# P-MT3620RDB-1-6_PMU.net
KiCad netlist of a schematic drawn in Altium Designer
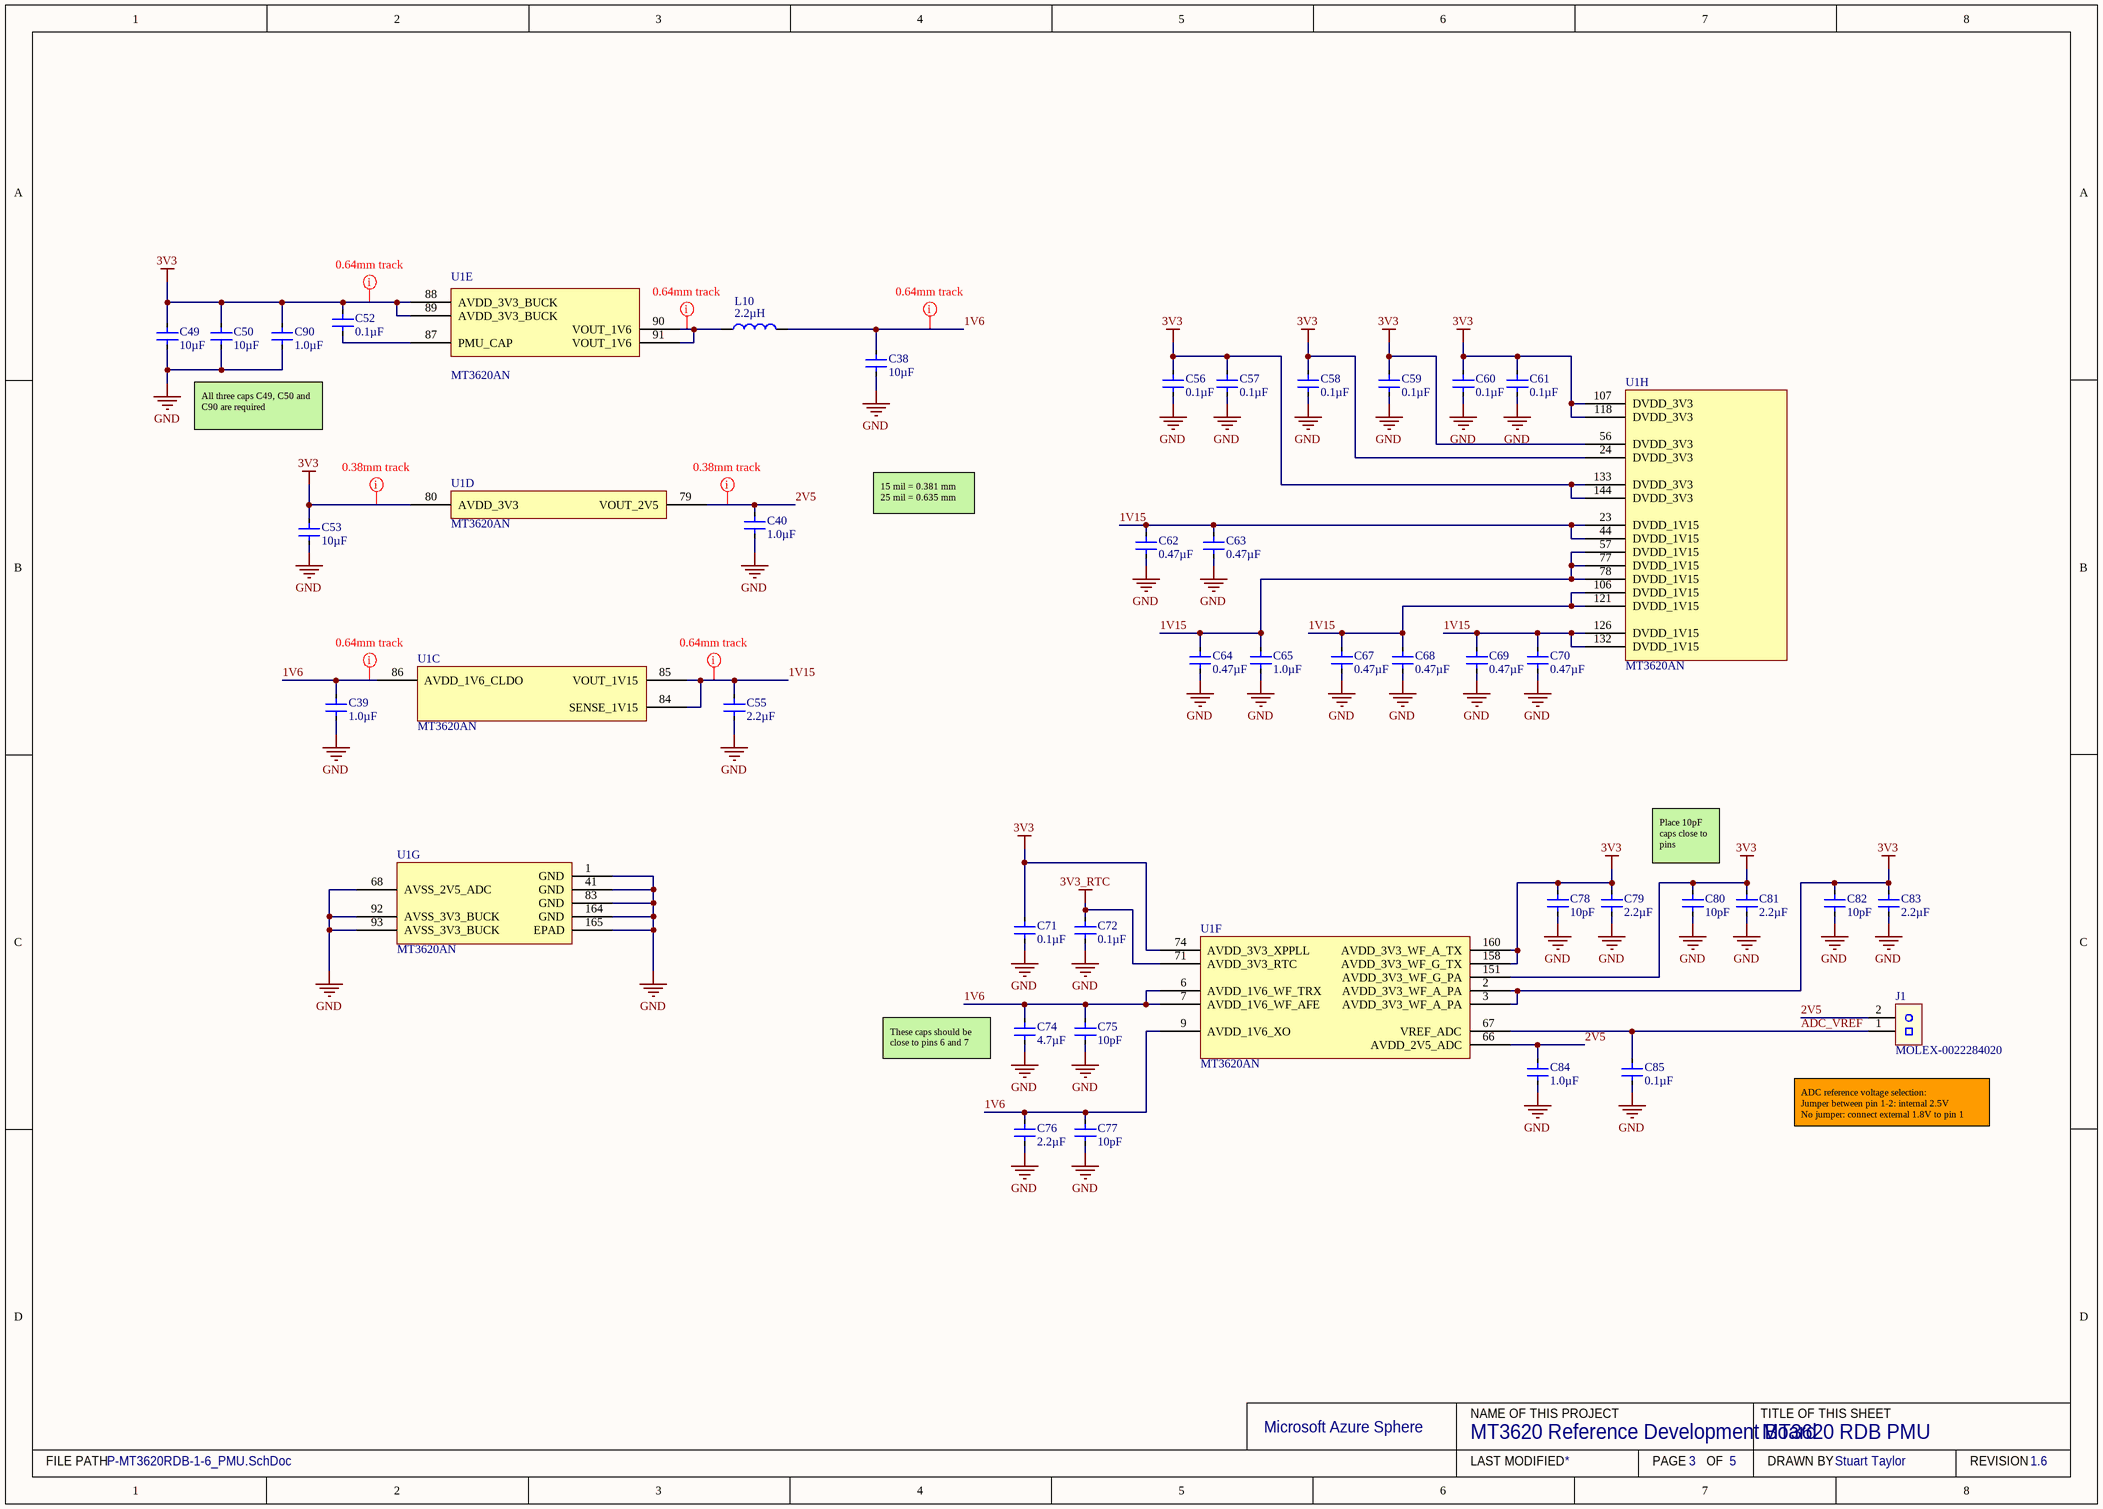
[diagram p0: P-MT3620RDB-1-6_PMU.SchDoc]

(export (version "E")
  (design (tool "Eeschema 10.0.6"))
  (components
    (comp (ref "C38")
      (value "10µF")
      (footprint "CAPC1608-EIA0603-1MM-MED")
      (description "CAP CER 10UF 25V 20% X5R 0603")
      (fields
        (field (name "MANUFACTURER") "TDK Corporation")
        (field (name "MANUFACTURER PART NUMBER") "C1608X5R1E106M080AC")
        (field (name "CAPACITANCE") "10µF")
      )
      (libsource (lib "TDK-Capacitor_C_0603") (part "10µF 0603 X5R 25V"))
    )
    (comp (ref "C39")
      (value "1.0µF")
      (footprint "CAPC1005-EIA0402 0.55MM MED")
      (description "CAP CER 1UF 35V 10% X5R 0402")
      (fields
        (field (name "MANUFACTURER") "TDK Corporation")
        (field (name "MANUFACTURER PART NUMBER") "C1005X5R1V105K050BC")
        (field (name "CAPACITANCE") "1.0µF")
      )
      (libsource (lib "TDK_Capacitor_C_0402") (part "1.0µF 0402 X5R 35V"))
    )
    (comp (ref "C40")
      (value "1.0µF")
      (footprint "CAPC1005-EIA0402 0.55MM MED")
      (description "CAP CER 1UF 35V 10% X5R 0402")
      (fields
        (field (name "MANUFACTURER") "TDK Corporation")
        (field (name "MANUFACTURER PART NUMBER") "C1005X5R1V105K050BC")
        (field (name "CAPACITANCE") "1.0µF")
      )
      (libsource (lib "TDK_Capacitor_C_0402") (part "1.0µF 0402 X5R 35V"))
    )
    (comp (ref "C49")
      (value "10µF")
      (footprint "CAPC1005-EIA0402 0.55MM MED")
      (description "CAP CER 10UF 6.3V 20% X5R 0402")
      (fields
        (field (name "MANUFACTURER") "TDK Corporation")
        (field (name "MANUFACTURER PART NUMBER") "C1005X5R0J106M050BC")
        (field (name "CAPACITANCE") "10µF")
      )
      (libsource (lib "TDK_Capacitor_C_0402") (part "10µF 0402 X5R 6.3V"))
    )
    (comp (ref "C50")
      (value "10µF")
      (footprint "CAPC1005-EIA0402 0.55MM MED")
      (description "CAP CER 10UF 6.3V 20% X5R 0402")
      (fields
        (field (name "MANUFACTURER") "TDK Corporation")
        (field (name "MANUFACTURER PART NUMBER") "C1005X5R0J106M050BC")
        (field (name "CAPACITANCE") "10µF")
      )
      (libsource (lib "TDK_Capacitor_C_0402") (part "10µF 0402 X5R 6.3V"))
    )
    (comp (ref "C52")
      (value "0.1µF")
      (footprint "CAPC1005-EIA0402 0.55MM MED")
      (description "CAP CER 0.1UF 50V 10% X7R 0402")
      (fields
        (field (name "MANUFACTURER") "TDK Corporation")
        (field (name "MANUFACTURER PART NUMBER") "C1005X7R1H104K050BB")
        (field (name "CAPACITANCE") "0.1µF")
      )
      (libsource (lib "TDK_Capacitor_C_0402") (part "0.1µF 0402 X7R 50V"))
    )
    (comp (ref "C53")
      (value "10µF")
      (footprint "CAPC1005-EIA0402 0.55MM MED")
      (description "CAP CER 10UF 6.3V 20% X5R 0402")
      (fields
        (field (name "MANUFACTURER") "TDK Corporation")
        (field (name "MANUFACTURER PART NUMBER") "C1005X5R0J106M050BC")
        (field (name "CAPACITANCE") "10µF")
      )
      (libsource (lib "TDK_Capacitor_C_0402") (part "10µF 0402 X5R 6.3V"))
    )
    (comp (ref "C55")
      (value "2.2µF")
      (footprint "CAPC1005-EIA0402 0.55MM MED")
      (description "CAP CER 2.2UF 35V 10% X5R 0402")
      (fields
        (field (name "MANUFACTURER") "TDK Corporation")
        (field (name "MANUFACTURER PART NUMBER") "C1005X5R1V225K050BC")
        (field (name "CAPACITANCE") "2.2µF")
      )
      (libsource (lib "TDK_Capacitor_C_0402") (part "2.2µF 0402 X5R 35V"))
    )
    (comp (ref "C56")
      (value "0.1µF")
      (footprint "CAPC1005-EIA0402 0.55MM MED")
      (description "CAP CER 0.1UF 50V 10% X7R 0402")
      (fields
        (field (name "MANUFACTURER") "TDK Corporation")
        (field (name "MANUFACTURER PART NUMBER") "C1005X7R1H104K050BB")
        (field (name "CAPACITANCE") "0.1µF")
      )
      (libsource (lib "TDK_Capacitor_C_0402") (part "0.1µF 0402 X7R 50V"))
    )
    (comp (ref "C57")
      (value "0.1µF")
      (footprint "CAPC1005-EIA0402 0.55MM MED")
      (description "CAP CER 0.1UF 50V 10% X7R 0402")
      (fields
        (field (name "MANUFACTURER") "TDK Corporation")
        (field (name "MANUFACTURER PART NUMBER") "C1005X7R1H104K050BB")
        (field (name "CAPACITANCE") "0.1µF")
      )
      (libsource (lib "TDK_Capacitor_C_0402") (part "0.1µF 0402 X7R 50V"))
    )
    (comp (ref "C58")
      (value "0.1µF")
      (footprint "CAPC1005-EIA0402 0.55MM MED")
      (description "CAP CER 0.1UF 50V 10% X7R 0402")
      (fields
        (field (name "MANUFACTURER") "TDK Corporation")
        (field (name "MANUFACTURER PART NUMBER") "C1005X7R1H104K050BB")
        (field (name "CAPACITANCE") "0.1µF")
      )
      (libsource (lib "TDK_Capacitor_C_0402") (part "0.1µF 0402 X7R 50V"))
    )
    (comp (ref "C59")
      (value "0.1µF")
      (footprint "CAPC1005-EIA0402 0.55MM MED")
      (description "CAP CER 0.1UF 50V 10% X7R 0402")
      (fields
        (field (name "MANUFACTURER") "TDK Corporation")
        (field (name "MANUFACTURER PART NUMBER") "C1005X7R1H104K050BB")
        (field (name "CAPACITANCE") "0.1µF")
      )
      (libsource (lib "TDK_Capacitor_C_0402") (part "0.1µF 0402 X7R 50V"))
    )
    (comp (ref "C60")
      (value "0.1µF")
      (footprint "CAPC1005-EIA0402 0.55MM MED")
      (description "CAP CER 0.1UF 50V 10% X7R 0402")
      (fields
        (field (name "MANUFACTURER") "TDK Corporation")
        (field (name "MANUFACTURER PART NUMBER") "C1005X7R1H104K050BB")
        (field (name "CAPACITANCE") "0.1µF")
      )
      (libsource (lib "TDK_Capacitor_C_0402") (part "0.1µF 0402 X7R 50V"))
    )
    (comp (ref "C61")
      (value "0.1µF")
      (footprint "CAPC1005-EIA0402 0.55MM MED")
      (description "CAP CER 0.1UF 50V 10% X7R 0402")
      (fields
        (field (name "MANUFACTURER") "TDK Corporation")
        (field (name "MANUFACTURER PART NUMBER") "C1005X7R1H104K050BB")
        (field (name "CAPACITANCE") "0.1µF")
      )
      (libsource (lib "TDK_Capacitor_C_0402") (part "0.1µF 0402 X7R 50V"))
    )
    (comp (ref "C62")
      (value "0.47µF")
      (footprint "CAPC1005-EIA0402 0.55MM MED")
      (description "CAP CER 0.47UF 35V 10% X5R 0402")
      (fields
        (field (name "MANUFACTURER") "TDK Corporation")
        (field (name "MANUFACTURER PART NUMBER") "C1005X5R1V474K050BC")
        (field (name "CAPACITANCE") "0.47µF")
      )
      (libsource (lib "TDK_Capacitor_C_0402") (part "0.47µF 0402 X5R 35V"))
    )
    (comp (ref "C63")
      (value "0.47µF")
      (footprint "CAPC1005-EIA0402 0.55MM MED")
      (description "CAP CER 0.47UF 35V 10% X5R 0402")
      (fields
        (field (name "MANUFACTURER") "TDK Corporation")
        (field (name "MANUFACTURER PART NUMBER") "C1005X5R1V474K050BC")
        (field (name "CAPACITANCE") "0.47µF")
      )
      (libsource (lib "TDK_Capacitor_C_0402") (part "0.47µF 0402 X5R 35V"))
    )
    (comp (ref "C64")
      (value "0.47µF")
      (footprint "CAPC1005-EIA0402 0.55MM MED")
      (description "CAP CER 0.47UF 35V 10% X5R 0402")
      (fields
        (field (name "MANUFACTURER") "TDK Corporation")
        (field (name "MANUFACTURER PART NUMBER") "C1005X5R1V474K050BC")
        (field (name "CAPACITANCE") "0.47µF")
      )
      (libsource (lib "TDK_Capacitor_C_0402") (part "0.47µF 0402 X5R 35V"))
    )
    (comp (ref "C65")
      (value "1.0µF")
      (footprint "CAPC1005-EIA0402 0.55MM MED")
      (description "CAP CER 1UF 35V 10% X5R 0402")
      (fields
        (field (name "MANUFACTURER") "TDK Corporation")
        (field (name "MANUFACTURER PART NUMBER") "C1005X5R1V105K050BC")
        (field (name "CAPACITANCE") "1.0µF")
      )
      (libsource (lib "TDK_Capacitor_C_0402") (part "1.0µF 0402 X5R 35V"))
    )
    (comp (ref "C67")
      (value "0.47µF")
      (footprint "CAPC1005-EIA0402 0.55MM MED")
      (description "CAP CER 0.47UF 35V 10% X5R 0402")
      (fields
        (field (name "MANUFACTURER") "TDK Corporation")
        (field (name "MANUFACTURER PART NUMBER") "C1005X5R1V474K050BC")
        (field (name "CAPACITANCE") "0.47µF")
      )
      (libsource (lib "TDK_Capacitor_C_0402") (part "0.47µF 0402 X5R 35V"))
    )
    (comp (ref "C68")
      (value "0.47µF")
      (footprint "CAPC1005-EIA0402 0.55MM MED")
      (description "CAP CER 0.47UF 35V 10% X5R 0402")
      (fields
        (field (name "MANUFACTURER") "TDK Corporation")
        (field (name "MANUFACTURER PART NUMBER") "C1005X5R1V474K050BC")
        (field (name "CAPACITANCE") "0.47µF")
      )
      (libsource (lib "TDK_Capacitor_C_0402") (part "0.47µF 0402 X5R 35V"))
    )
    (comp (ref "C69")
      (value "0.47µF")
      (footprint "CAPC1005-EIA0402 0.55MM MED")
      (description "CAP CER 0.47UF 35V 10% X5R 0402")
      (fields
        (field (name "MANUFACTURER") "TDK Corporation")
        (field (name "MANUFACTURER PART NUMBER") "C1005X5R1V474K050BC")
        (field (name "CAPACITANCE") "0.47µF")
      )
      (libsource (lib "TDK_Capacitor_C_0402") (part "0.47µF 0402 X5R 35V"))
    )
    (comp (ref "C70")
      (value "0.47µF")
      (footprint "CAPC1005-EIA0402 0.55MM MED")
      (description "CAP CER 0.47UF 35V 10% X5R 0402")
      (fields
        (field (name "MANUFACTURER") "TDK Corporation")
        (field (name "MANUFACTURER PART NUMBER") "C1005X5R1V474K050BC")
        (field (name "CAPACITANCE") "0.47µF")
      )
      (libsource (lib "TDK_Capacitor_C_0402") (part "0.47µF 0402 X5R 35V"))
    )
    (comp (ref "C71")
      (value "0.1µF")
      (footprint "CAPC1005-EIA0402 0.55MM MED")
      (description "CAP CER 0.1UF 50V 10% X7R 0402")
      (fields
        (field (name "MANUFACTURER") "TDK Corporation")
        (field (name "MANUFACTURER PART NUMBER") "C1005X7R1H104K050BB")
        (field (name "CAPACITANCE") "0.1µF")
      )
      (libsource (lib "TDK_Capacitor_C_0402") (part "0.1µF 0402 X7R 50V"))
    )
    (comp (ref "C72")
      (value "0.1µF")
      (footprint "CAPC1005-EIA0402 0.55MM MED")
      (description "CAP CER 0.1UF 50V 10% X7R 0402")
      (fields
        (field (name "MANUFACTURER") "TDK Corporation")
        (field (name "MANUFACTURER PART NUMBER") "C1005X7R1H104K050BB")
        (field (name "CAPACITANCE") "0.1µF")
      )
      (libsource (lib "TDK_Capacitor_C_0402") (part "0.1µF 0402 X7R 50V"))
    )
    (comp (ref "C74")
      (value "4.7µF")
      (footprint "CAPC1005-EIA0402 0.55MM MED")
      (description "CAP CER 4.7UF 10V 10% X5R 0402")
      (fields
        (field (name "MANUFACTURER") "TDK Corporation")
        (field (name "MANUFACTURER PART NUMBER") "C1005X5R1A475K050BC")
        (field (name "CAPACITANCE") "4.7µF")
      )
      (libsource (lib "TDK_Capacitor_C_0402") (part "4.7µF 0402 X5R 10V"))
    )
    (comp (ref "C75")
      (value "10pF")
      (footprint "CAPC1005-EIA0402 0.55MM MED")
      (description "CAP CER 10PF 50V NP0 0402")
      (fields
        (field (name "MANUFACTURER") "TDK Corporation")
        (field (name "MANUFACTURER PART NUMBER") "C1005C0G1H100D050BA")
        (field (name "CAPACITANCE") "10pF")
      )
      (libsource (lib "TDK_Capacitor_C_0402") (part "10pF 0402 C0G, NP0 50V"))
    )
    (comp (ref "C76")
      (value "2.2µF")
      (footprint "CAPC1005-EIA0402 0.55MM MED")
      (description "CAP CER 2.2UF 35V 10% X5R 0402")
      (fields
        (field (name "MANUFACTURER") "TDK Corporation")
        (field (name "MANUFACTURER PART NUMBER") "C1005X5R1V225K050BC")
        (field (name "CAPACITANCE") "2.2µF")
      )
      (libsource (lib "TDK_Capacitor_C_0402") (part "2.2µF 0402 X5R 35V"))
    )
    (comp (ref "C77")
      (value "10pF")
      (footprint "CAPC1005-EIA0402 0.55MM MED")
      (description "CAP CER 10PF 50V NP0 0402")
      (fields
        (field (name "MANUFACTURER") "TDK Corporation")
        (field (name "MANUFACTURER PART NUMBER") "C1005C0G1H100D050BA")
        (field (name "CAPACITANCE") "10pF")
      )
      (libsource (lib "TDK_Capacitor_C_0402") (part "10pF 0402 C0G, NP0 50V"))
    )
    (comp (ref "C78")
      (value "10pF")
      (footprint "CAPC1005-EIA0402 0.55MM MED")
      (description "CAP CER 10PF 50V NP0 0402")
      (fields
        (field (name "MANUFACTURER") "TDK Corporation")
        (field (name "MANUFACTURER PART NUMBER") "C1005C0G1H100D050BA")
        (field (name "CAPACITANCE") "10pF")
      )
      (libsource (lib "TDK_Capacitor_C_0402") (part "10pF 0402 C0G, NP0 50V"))
    )
    (comp (ref "C79")
      (value "2.2µF")
      (footprint "CAPC1005-EIA0402 0.55MM MED")
      (description "CAP CER 2.2UF 35V 10% X5R 0402")
      (fields
        (field (name "MANUFACTURER") "TDK Corporation")
        (field (name "MANUFACTURER PART NUMBER") "C1005X5R1V225K050BC")
        (field (name "CAPACITANCE") "2.2µF")
      )
      (libsource (lib "TDK_Capacitor_C_0402") (part "2.2µF 0402 X5R 35V"))
    )
    (comp (ref "C80")
      (value "10pF")
      (footprint "CAPC1005-EIA0402 0.55MM MED")
      (description "CAP CER 10PF 50V NP0 0402")
      (fields
        (field (name "MANUFACTURER") "TDK Corporation")
        (field (name "MANUFACTURER PART NUMBER") "C1005C0G1H100D050BA")
        (field (name "CAPACITANCE") "10pF")
      )
      (libsource (lib "TDK_Capacitor_C_0402") (part "10pF 0402 C0G, NP0 50V"))
    )
    (comp (ref "C81")
      (value "2.2µF")
      (footprint "CAPC1005-EIA0402 0.55MM MED")
      (description "CAP CER 2.2UF 35V 10% X5R 0402")
      (fields
        (field (name "MANUFACTURER") "TDK Corporation")
        (field (name "MANUFACTURER PART NUMBER") "C1005X5R1V225K050BC")
        (field (name "CAPACITANCE") "2.2µF")
      )
      (libsource (lib "TDK_Capacitor_C_0402") (part "2.2µF 0402 X5R 35V"))
    )
    (comp (ref "C82")
      (value "10pF")
      (footprint "CAPC1005-EIA0402 0.55MM MED")
      (description "CAP CER 10PF 50V NP0 0402")
      (fields
        (field (name "MANUFACTURER") "TDK Corporation")
        (field (name "MANUFACTURER PART NUMBER") "C1005C0G1H100D050BA")
        (field (name "CAPACITANCE") "10pF")
      )
      (libsource (lib "TDK_Capacitor_C_0402") (part "10pF 0402 C0G, NP0 50V"))
    )
    (comp (ref "C83")
      (value "2.2µF")
      (footprint "CAPC1005-EIA0402 0.55MM MED")
      (description "CAP CER 2.2UF 35V 10% X5R 0402")
      (fields
        (field (name "MANUFACTURER") "TDK Corporation")
        (field (name "MANUFACTURER PART NUMBER") "C1005X5R1V225K050BC")
        (field (name "CAPACITANCE") "2.2µF")
      )
      (libsource (lib "TDK_Capacitor_C_0402") (part "2.2µF 0402 X5R 35V"))
    )
    (comp (ref "C84")
      (value "1.0µF")
      (footprint "CAPC1005-EIA0402 0.55MM MED")
      (description "CAP CER 1UF 35V 10% X5R 0402")
      (fields
        (field (name "MANUFACTURER") "TDK Corporation")
        (field (name "MANUFACTURER PART NUMBER") "C1005X5R1V105K050BC")
        (field (name "CAPACITANCE") "1.0µF")
      )
      (libsource (lib "TDK_Capacitor_C_0402") (part "1.0µF 0402 X5R 35V"))
    )
    (comp (ref "C85")
      (value "0.1µF")
      (footprint "CAPC1005-EIA0402 0.55MM MED")
      (description "CAP CER 0.1UF 50V 10% X7R 0402")
      (fields
        (field (name "MANUFACTURER") "TDK Corporation")
        (field (name "MANUFACTURER PART NUMBER") "C1005X7R1H104K050BB")
        (field (name "CAPACITANCE") "0.1µF")
      )
      (libsource (lib "TDK_Capacitor_C_0402") (part "0.1µF 0402 X7R 50V"))
    )
    (comp (ref "C90")
      (value "1.0µF")
      (footprint "CAPC1005-EIA0402 0.55MM MED")
      (description "CAP CER 1UF 35V 10% X5R 0402")
      (fields
        (field (name "MANUFACTURER") "TDK Corporation")
        (field (name "MANUFACTURER PART NUMBER") "C1005X5R1V105K050BC")
        (field (name "CAPACITANCE") "1.0µF")
      )
      (libsource (lib "TDK_Capacitor_C_0402") (part "1.0µF 0402 X5R 35V"))
    )
    (comp (ref "J1")
      (value "MOLEX-0022284020")
      (footprint "0022284020")
      (description "CONN HEADER 2POS .100 VERT TIN")
      (fields
        (field (name "MANUFACTURER") "Molex, LLC")
        (field (name "MANUFACTURER PART NUMBER") "0022284020")
      )
      (libsource (lib "Molex") (part "MOLEX-0022284020"))
    )
    (comp (ref "L10")
      (value "2.2µH")
      (footprint "MAMK2520T2R2M")
      (description "FIXED IND 2.2UH 1.9A 117 MOHM")
      (fields
        (field (name "MANUFACTURER") "Taiyo Yuden")
        (field (name "MANUFACTURER PART NUMBER") "MAMK2520T2R2M")
      )
      (libsource (lib "TaiyoYuden ") (part "MAMK2520T2R2M"))
    )
    (comp (ref "U1")
      (value "MT3620AN")
      (footprint "MT3620_MaskSquaresVias50")
      (fields (field (name "MANUFACTURER") "MediaTek Inc."))
      (libsource (lib "Microsoft") (part "MT3620AN"))
    )
  )
  (nets
    (net (code "1") (name "/1V6") (class "Default")
      (node (ref "C38") (pin "2") (pinfunction "2_2") (pintype "passive"))
      (node (ref "C39") (pin "2") (pinfunction "2_2") (pintype "passive"))
      (node (ref "C74") (pin "2") (pinfunction "2_2") (pintype "passive"))
      (node (ref "C75") (pin "2") (pinfunction "2_2") (pintype "passive"))
      (node (ref "C76") (pin "2") (pinfunction "2_2") (pintype "passive"))
      (node (ref "C77") (pin "2") (pinfunction "2_2") (pintype "passive"))
      (node (ref "L10") (pin "2") (pinfunction "2_2") (pintype "passive"))
      (node (ref "U1") (pin "6") (pinfunction "AVDD_1V6_WF_TRX_6") (pintype "passive"))
      (node (ref "U1") (pin "7") (pinfunction "AVDD_1V6_WF_AFE_7") (pintype "passive"))
      (node (ref "U1") (pin "86") (pinfunction "AVDD_1V6_CLDO_86") (pintype "passive"))
      (node (ref "U1") (pin "9") (pinfunction "AVDD_1V6_XO_9") (pintype "passive"))
    )
    (net (code "2") (name "/1V15") (class "Default")
      (node (ref "C55") (pin "2") (pinfunction "2_2") (pintype "passive"))
      (node (ref "C62") (pin "2") (pinfunction "2_2") (pintype "passive"))
      (node (ref "C63") (pin "2") (pinfunction "2_2") (pintype "passive"))
      (node (ref "C64") (pin "2") (pinfunction "2_2") (pintype "passive"))
      (node (ref "C65") (pin "2") (pinfunction "2_2") (pintype "passive"))
      (node (ref "C67") (pin "2") (pinfunction "2_2") (pintype "passive"))
      (node (ref "C68") (pin "2") (pinfunction "2_2") (pintype "passive"))
      (node (ref "C69") (pin "2") (pinfunction "2_2") (pintype "passive"))
      (node (ref "C70") (pin "2") (pinfunction "2_2") (pintype "passive"))
      (node (ref "U1") (pin "106") (pinfunction "DVDD_1V15_106") (pintype "passive"))
      (node (ref "U1") (pin "121") (pinfunction "DVDD_1V15_121") (pintype "passive"))
      (node (ref "U1") (pin "126") (pinfunction "DVDD_1V15_126") (pintype "passive"))
      (node (ref "U1") (pin "132") (pinfunction "DVDD_1V15_132") (pintype "passive"))
      (node (ref "U1") (pin "23") (pinfunction "DVDD_1V15_23") (pintype "passive"))
      (node (ref "U1") (pin "44") (pinfunction "DVDD_1V15_44") (pintype "passive"))
      (node (ref "U1") (pin "57") (pinfunction "DVDD_1V15_57") (pintype "passive"))
      (node (ref "U1") (pin "77") (pinfunction "DVDD_1V15_77") (pintype "passive"))
      (node (ref "U1") (pin "78") (pinfunction "DVDD_1V15_78") (pintype "passive"))
      (node (ref "U1") (pin "84") (pinfunction "SENSE_1V15_84") (pintype "passive"))
      (node (ref "U1") (pin "85") (pinfunction "VOUT_1V15_85") (pintype "passive"))
    )
    (net (code "3") (name "/2V5") (class "Default")
      (node (ref "C40") (pin "2") (pinfunction "2_2") (pintype "passive"))
      (node (ref "C84") (pin "2") (pinfunction "2_2") (pintype "passive"))
      (node (ref "J1") (pin "2") (pinfunction "2_2") (pintype "passive"))
      (node (ref "U1") (pin "66") (pinfunction "AVDD_2V5_ADC_66") (pintype "passive"))
      (node (ref "U1") (pin "79") (pinfunction "VOUT_2V5_79") (pintype "passive"))
    )
    (net (code "4") (name "/ADC_VREF") (class "Default")
      (node (ref "C85") (pin "2") (pinfunction "2_2") (pintype "passive"))
      (node (ref "J1") (pin "1") (pinfunction "1_1") (pintype "passive"))
      (node (ref "U1") (pin "67") (pinfunction "VREF_ADC_67") (pintype "passive"))
    )
    (net (code "5") (name "3V3") (class "Default")
      (node (ref "C49") (pin "2") (pinfunction "2_2") (pintype "passive"))
      (node (ref "C50") (pin "2") (pinfunction "2_2") (pintype "passive"))
      (node (ref "C52") (pin "2") (pinfunction "2_2") (pintype "passive"))
      (node (ref "C53") (pin "2") (pinfunction "2_2") (pintype "passive"))
      (node (ref "C56") (pin "2") (pinfunction "2_2") (pintype "passive"))
      (node (ref "C57") (pin "2") (pinfunction "2_2") (pintype "passive"))
      (node (ref "C58") (pin "2") (pinfunction "2_2") (pintype "passive"))
      (node (ref "C59") (pin "2") (pinfunction "2_2") (pintype "passive"))
      (node (ref "C60") (pin "2") (pinfunction "2_2") (pintype "passive"))
      (node (ref "C61") (pin "2") (pinfunction "2_2") (pintype "passive"))
      (node (ref "C71") (pin "2") (pinfunction "2_2") (pintype "passive"))
      (node (ref "C78") (pin "2") (pinfunction "2_2") (pintype "passive"))
      (node (ref "C79") (pin "2") (pinfunction "2_2") (pintype "passive"))
      (node (ref "C80") (pin "2") (pinfunction "2_2") (pintype "passive"))
      (node (ref "C81") (pin "2") (pinfunction "2_2") (pintype "passive"))
      (node (ref "C82") (pin "2") (pinfunction "2_2") (pintype "passive"))
      (node (ref "C83") (pin "2") (pinfunction "2_2") (pintype "passive"))
      (node (ref "C90") (pin "2") (pinfunction "2_2") (pintype "passive"))
      (node (ref "U1") (pin "107") (pinfunction "DVDD_3V3_107") (pintype "passive"))
      (node (ref "U1") (pin "118") (pinfunction "DVDD_3V3_118") (pintype "passive"))
      (node (ref "U1") (pin "133") (pinfunction "DVDD_3V3_133") (pintype "passive"))
      (node (ref "U1") (pin "144") (pinfunction "DVDD_3V3_144") (pintype "passive"))
      (node (ref "U1") (pin "151") (pinfunction "AVDD_3V3_WF_G_PA_151") (pintype "passive"))
      (node (ref "U1") (pin "158") (pinfunction "AVDD_3V3_WF_G_TX_158") (pintype "passive"))
      (node (ref "U1") (pin "160") (pinfunction "AVDD_3V3_WF_A_TX_160") (pintype "passive"))
      (node (ref "U1") (pin "2") (pinfunction "AVDD_3V3_WF_A_PA_2") (pintype "passive"))
      (node (ref "U1") (pin "24") (pinfunction "DVDD_3V3_24") (pintype "passive"))
      (node (ref "U1") (pin "3") (pinfunction "AVDD_3V3_WF_A_PA_3") (pintype "passive"))
      (node (ref "U1") (pin "56") (pinfunction "DVDD_3V3_56") (pintype "passive"))
      (node (ref "U1") (pin "74") (pinfunction "AVDD_3V3_XPPLL_74") (pintype "passive"))
      (node (ref "U1") (pin "80") (pinfunction "AVDD_3V3_80") (pintype "passive"))
      (node (ref "U1") (pin "88") (pinfunction "AVDD_3V3_BUCK_88") (pintype "passive"))
      (node (ref "U1") (pin "89") (pinfunction "AVDD_3V3_BUCK_89") (pintype "passive"))
    )
    (net (code "6") (name "3V3_RTC") (class "Default")
      (node (ref "C72") (pin "2") (pinfunction "2_2") (pintype "passive"))
      (node (ref "U1") (pin "71") (pinfunction "AVDD_3V3_RTC_71") (pintype "passive"))
    )
    (net (code "7") (name "GND") (class "Default")
      (node (ref "C38") (pin "1") (pinfunction "1_1") (pintype "passive"))
      (node (ref "C39") (pin "1") (pinfunction "1_1") (pintype "passive"))
      (node (ref "C40") (pin "1") (pinfunction "1_1") (pintype "passive"))
      (node (ref "C49") (pin "1") (pinfunction "1_1") (pintype "passive"))
      (node (ref "C50") (pin "1") (pinfunction "1_1") (pintype "passive"))
      (node (ref "C53") (pin "1") (pinfunction "1_1") (pintype "passive"))
      (node (ref "C55") (pin "1") (pinfunction "1_1") (pintype "passive"))
      (node (ref "C56") (pin "1") (pinfunction "1_1") (pintype "passive"))
      (node (ref "C57") (pin "1") (pinfunction "1_1") (pintype "passive"))
      (node (ref "C58") (pin "1") (pinfunction "1_1") (pintype "passive"))
      (node (ref "C59") (pin "1") (pinfunction "1_1") (pintype "passive"))
      (node (ref "C60") (pin "1") (pinfunction "1_1") (pintype "passive"))
      (node (ref "C61") (pin "1") (pinfunction "1_1") (pintype "passive"))
      (node (ref "C62") (pin "1") (pinfunction "1_1") (pintype "passive"))
      (node (ref "C63") (pin "1") (pinfunction "1_1") (pintype "passive"))
      (node (ref "C64") (pin "1") (pinfunction "1_1") (pintype "passive"))
      (node (ref "C65") (pin "1") (pinfunction "1_1") (pintype "passive"))
      (node (ref "C67") (pin "1") (pinfunction "1_1") (pintype "passive"))
      (node (ref "C68") (pin "1") (pinfunction "1_1") (pintype "passive"))
      (node (ref "C69") (pin "1") (pinfunction "1_1") (pintype "passive"))
      (node (ref "C70") (pin "1") (pinfunction "1_1") (pintype "passive"))
      (node (ref "C71") (pin "1") (pinfunction "1_1") (pintype "passive"))
      (node (ref "C72") (pin "1") (pinfunction "1_1") (pintype "passive"))
      (node (ref "C74") (pin "1") (pinfunction "1_1") (pintype "passive"))
      (node (ref "C75") (pin "1") (pinfunction "1_1") (pintype "passive"))
      (node (ref "C76") (pin "1") (pinfunction "1_1") (pintype "passive"))
      (node (ref "C77") (pin "1") (pinfunction "1_1") (pintype "passive"))
      (node (ref "C78") (pin "1") (pinfunction "1_1") (pintype "passive"))
      (node (ref "C79") (pin "1") (pinfunction "1_1") (pintype "passive"))
      (node (ref "C80") (pin "1") (pinfunction "1_1") (pintype "passive"))
      (node (ref "C81") (pin "1") (pinfunction "1_1") (pintype "passive"))
      (node (ref "C82") (pin "1") (pinfunction "1_1") (pintype "passive"))
      (node (ref "C83") (pin "1") (pinfunction "1_1") (pintype "passive"))
      (node (ref "C84") (pin "1") (pinfunction "1_1") (pintype "passive"))
      (node (ref "C85") (pin "1") (pinfunction "1_1") (pintype "passive"))
      (node (ref "C90") (pin "1") (pinfunction "1_1") (pintype "passive"))
      (node (ref "U1") (pin "1") (pinfunction "GND_1") (pintype "passive"))
      (node (ref "U1") (pin "164") (pinfunction "GND_164") (pintype "passive"))
      (node (ref "U1") (pin "165") (pinfunction "EPAD_165") (pintype "passive"))
      (node (ref "U1") (pin "41") (pinfunction "GND_41") (pintype "passive"))
      (node (ref "U1") (pin "68") (pinfunction "AVSS_2V5_ADC_68") (pintype "passive"))
      (node (ref "U1") (pin "83") (pinfunction "GND_83") (pintype "passive"))
      (node (ref "U1") (pin "92") (pinfunction "AVSS_3V3_BUCK_92") (pintype "passive"))
      (node (ref "U1") (pin "93") (pinfunction "AVSS_3V3_BUCK_93") (pintype "passive"))
    )
    (net (code "8") (name "Net-(L10-Pad1)") (class "Default")
      (node (ref "L10") (pin "1") (pinfunction "1_1") (pintype "passive"))
      (node (ref "U1") (pin "90") (pinfunction "VOUT_1V6_90") (pintype "passive"))
      (node (ref "U1") (pin "91") (pinfunction "VOUT_1V6_91") (pintype "passive"))
    )
    (net (code "9") (name "Net-(U1E-PMU_CAP)") (class "Default")
      (node (ref "C52") (pin "1") (pinfunction "1_1") (pintype "passive"))
      (node (ref "U1") (pin "87") (pinfunction "PMU_CAP_87") (pintype "passive"))
    )
  )
)
